# OhmmeterV1_1.net
KiCad netlist of a schematic drawn in EasyEDA Pro
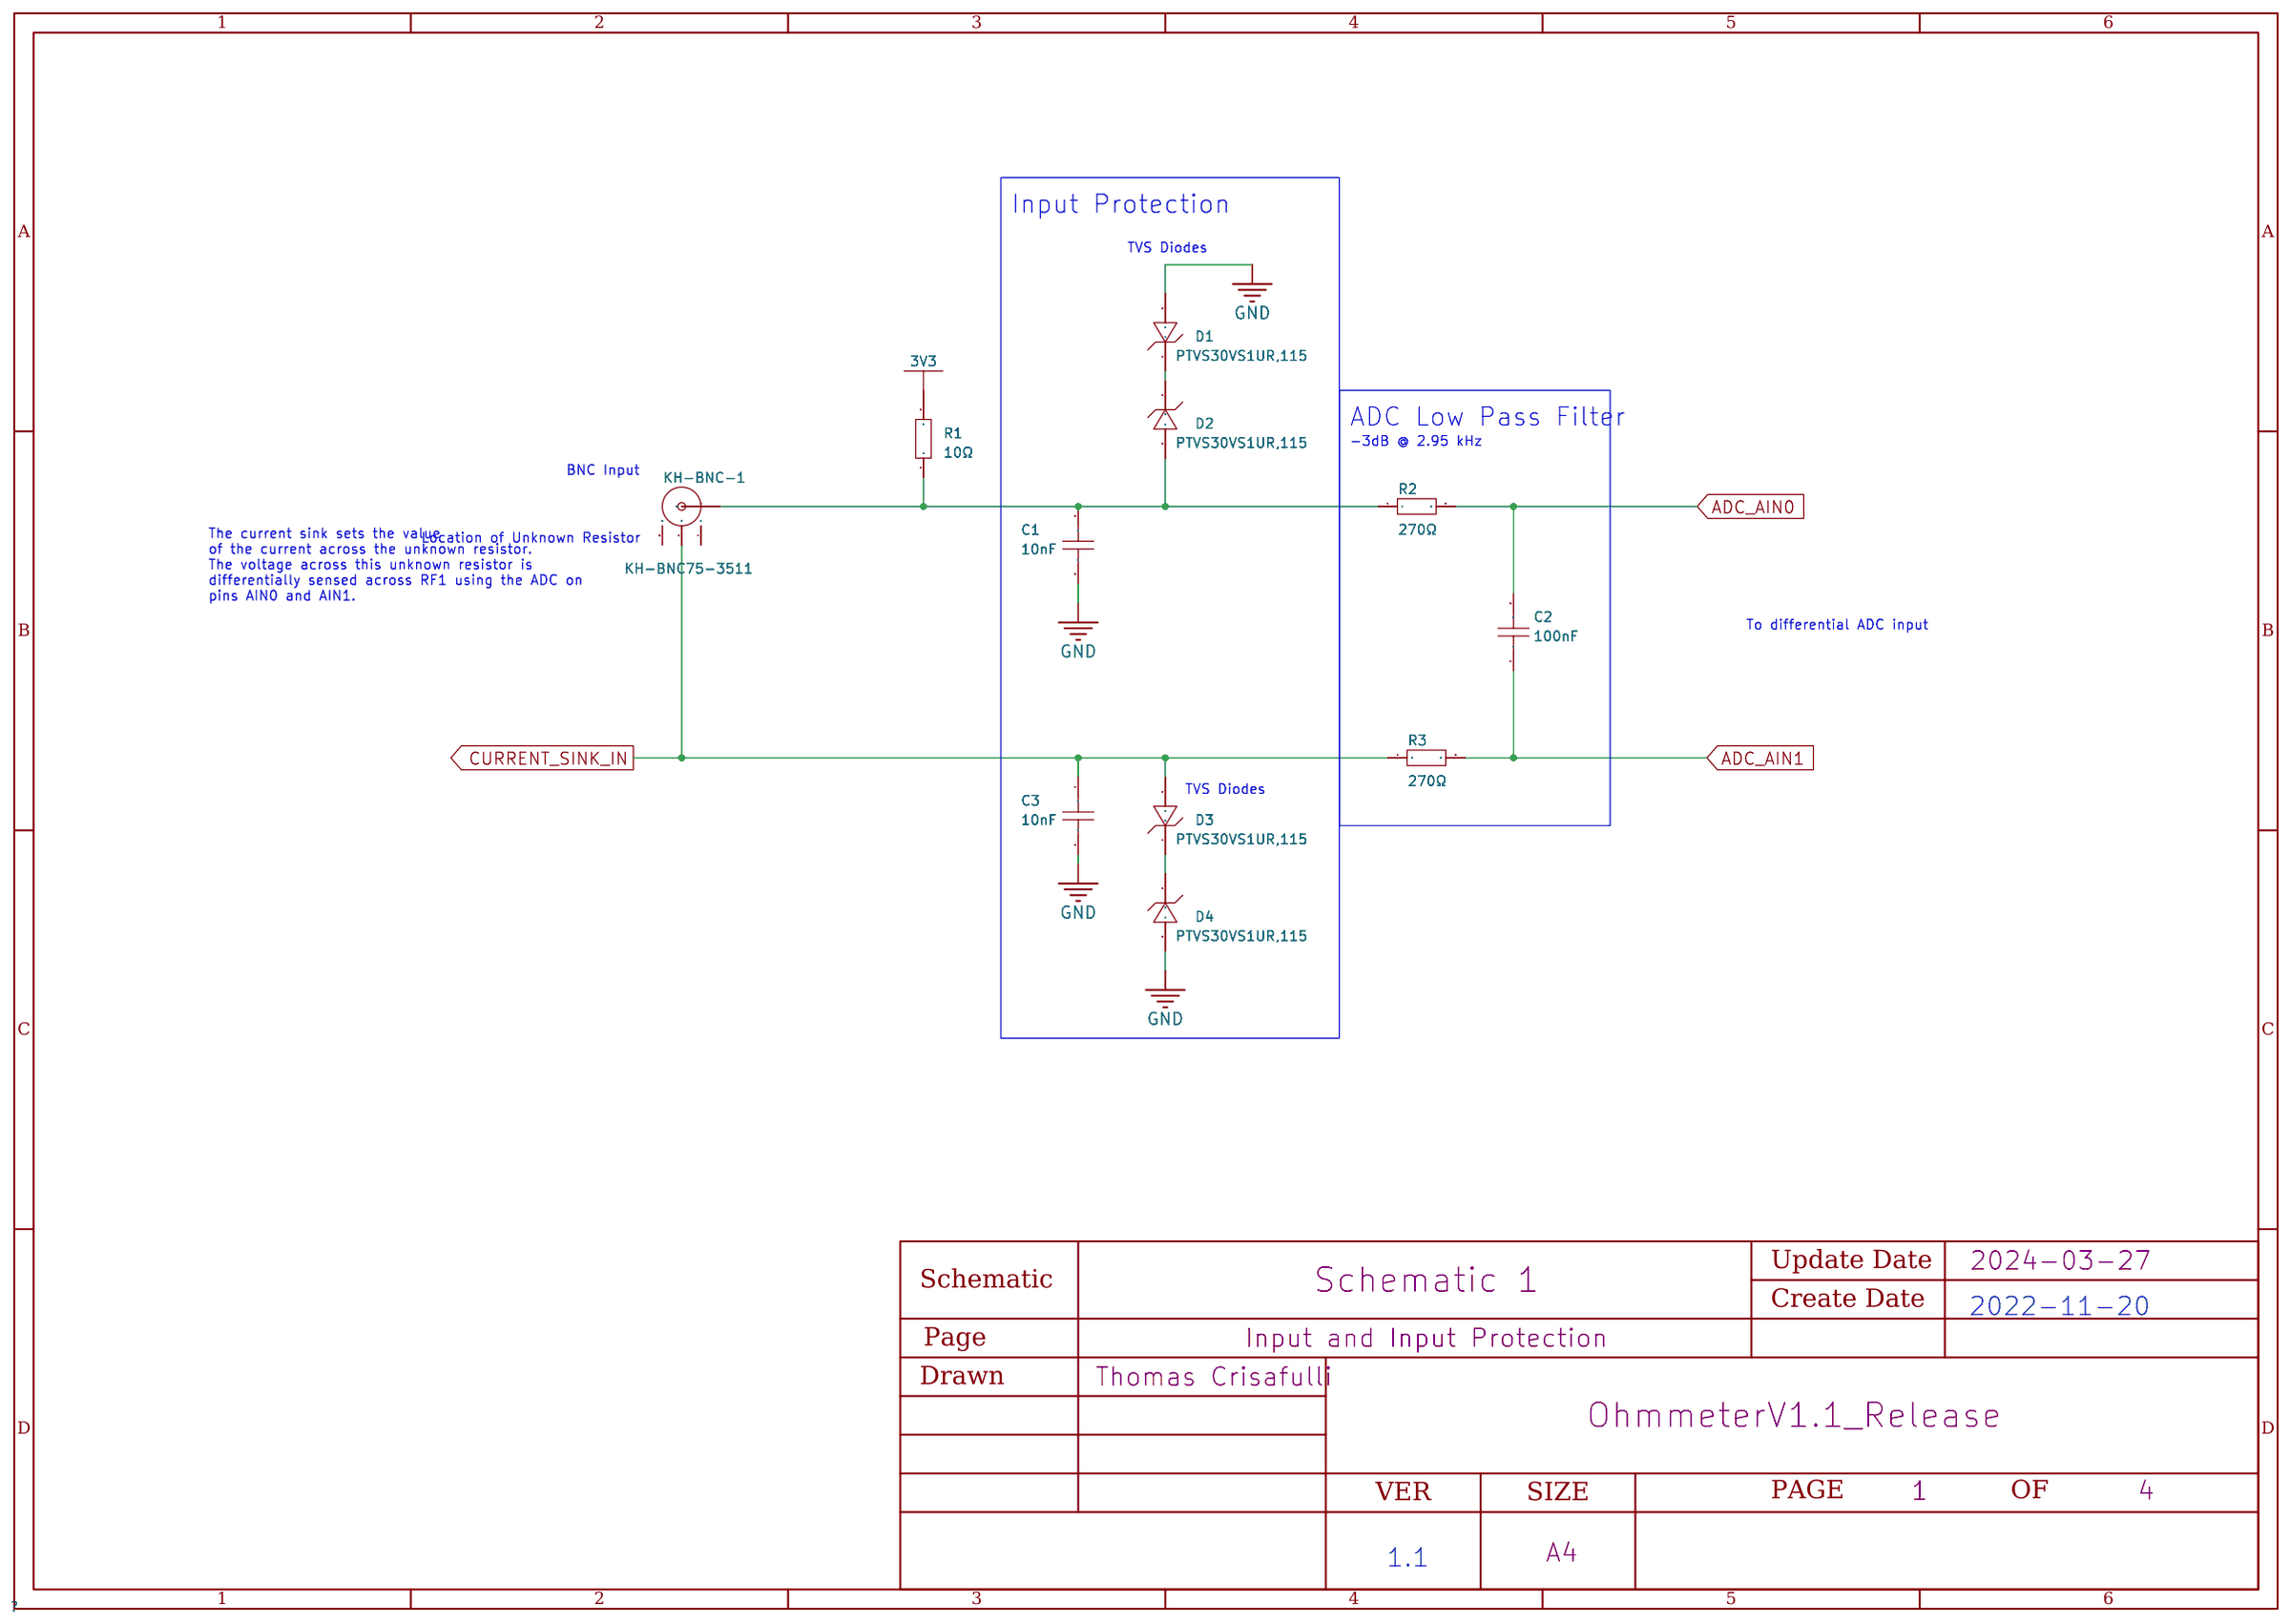
[diagram p0: Input and Input Protection]
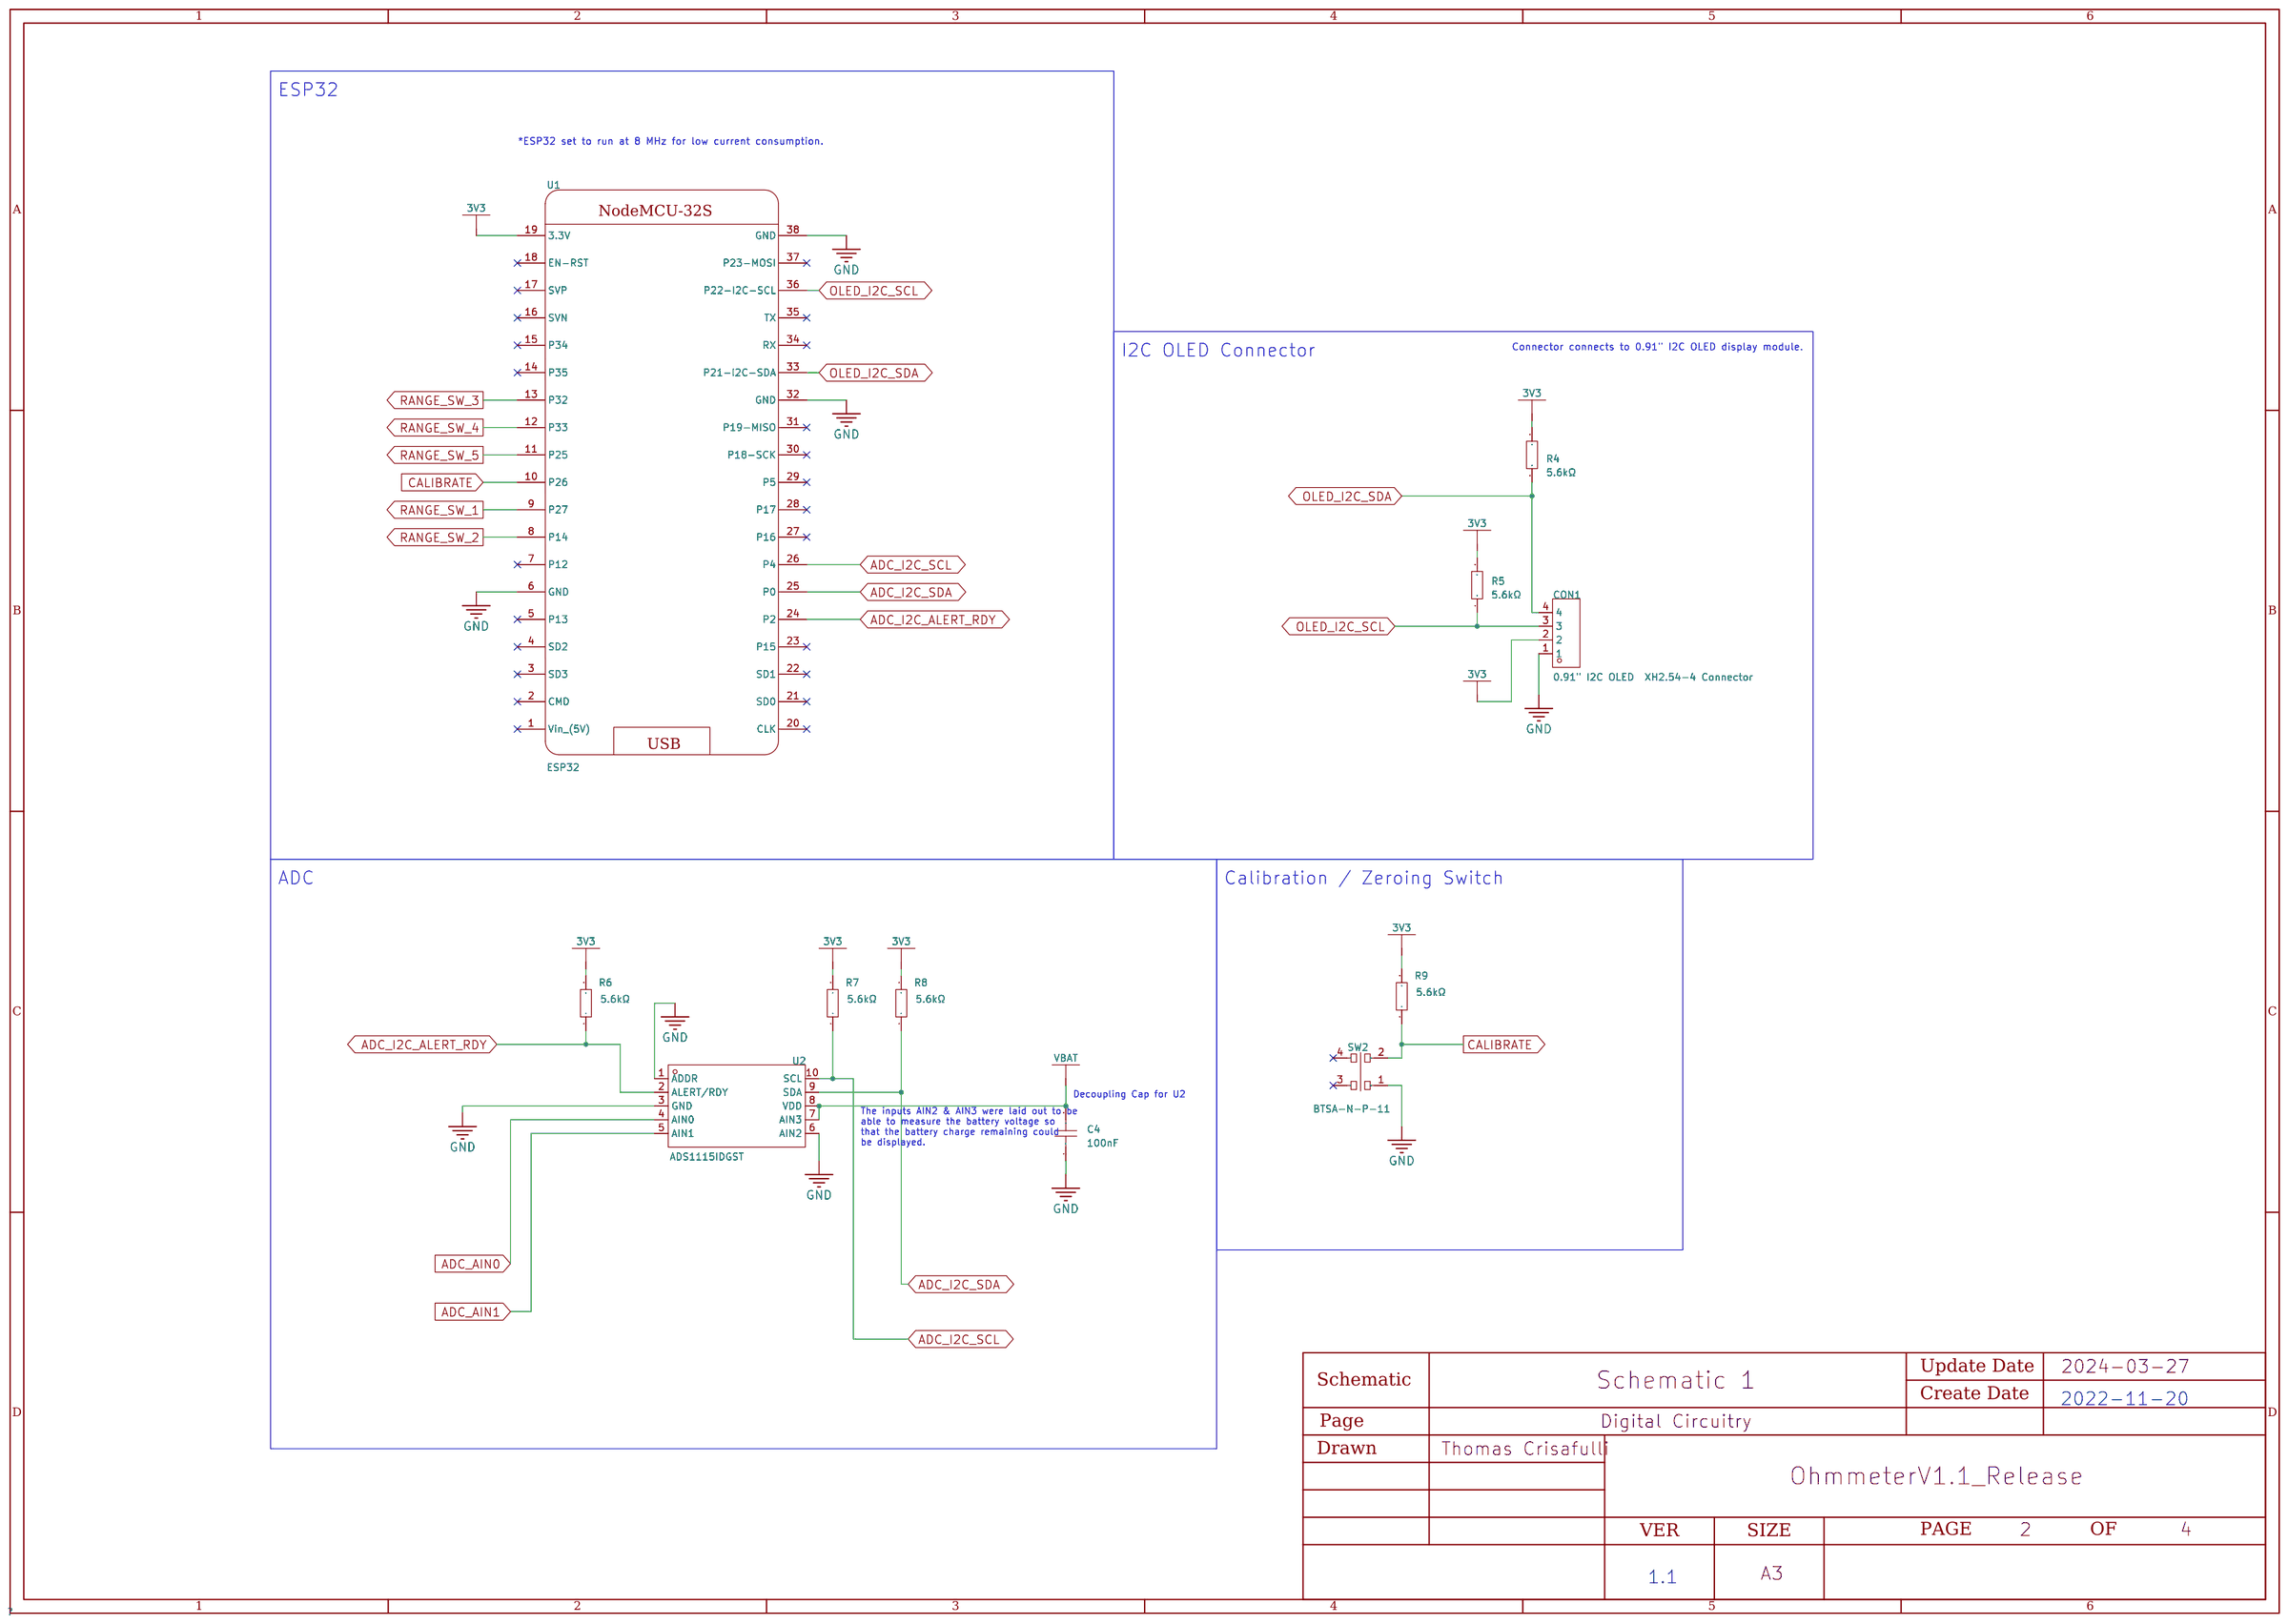
[diagram p1: Digital Circuitry]
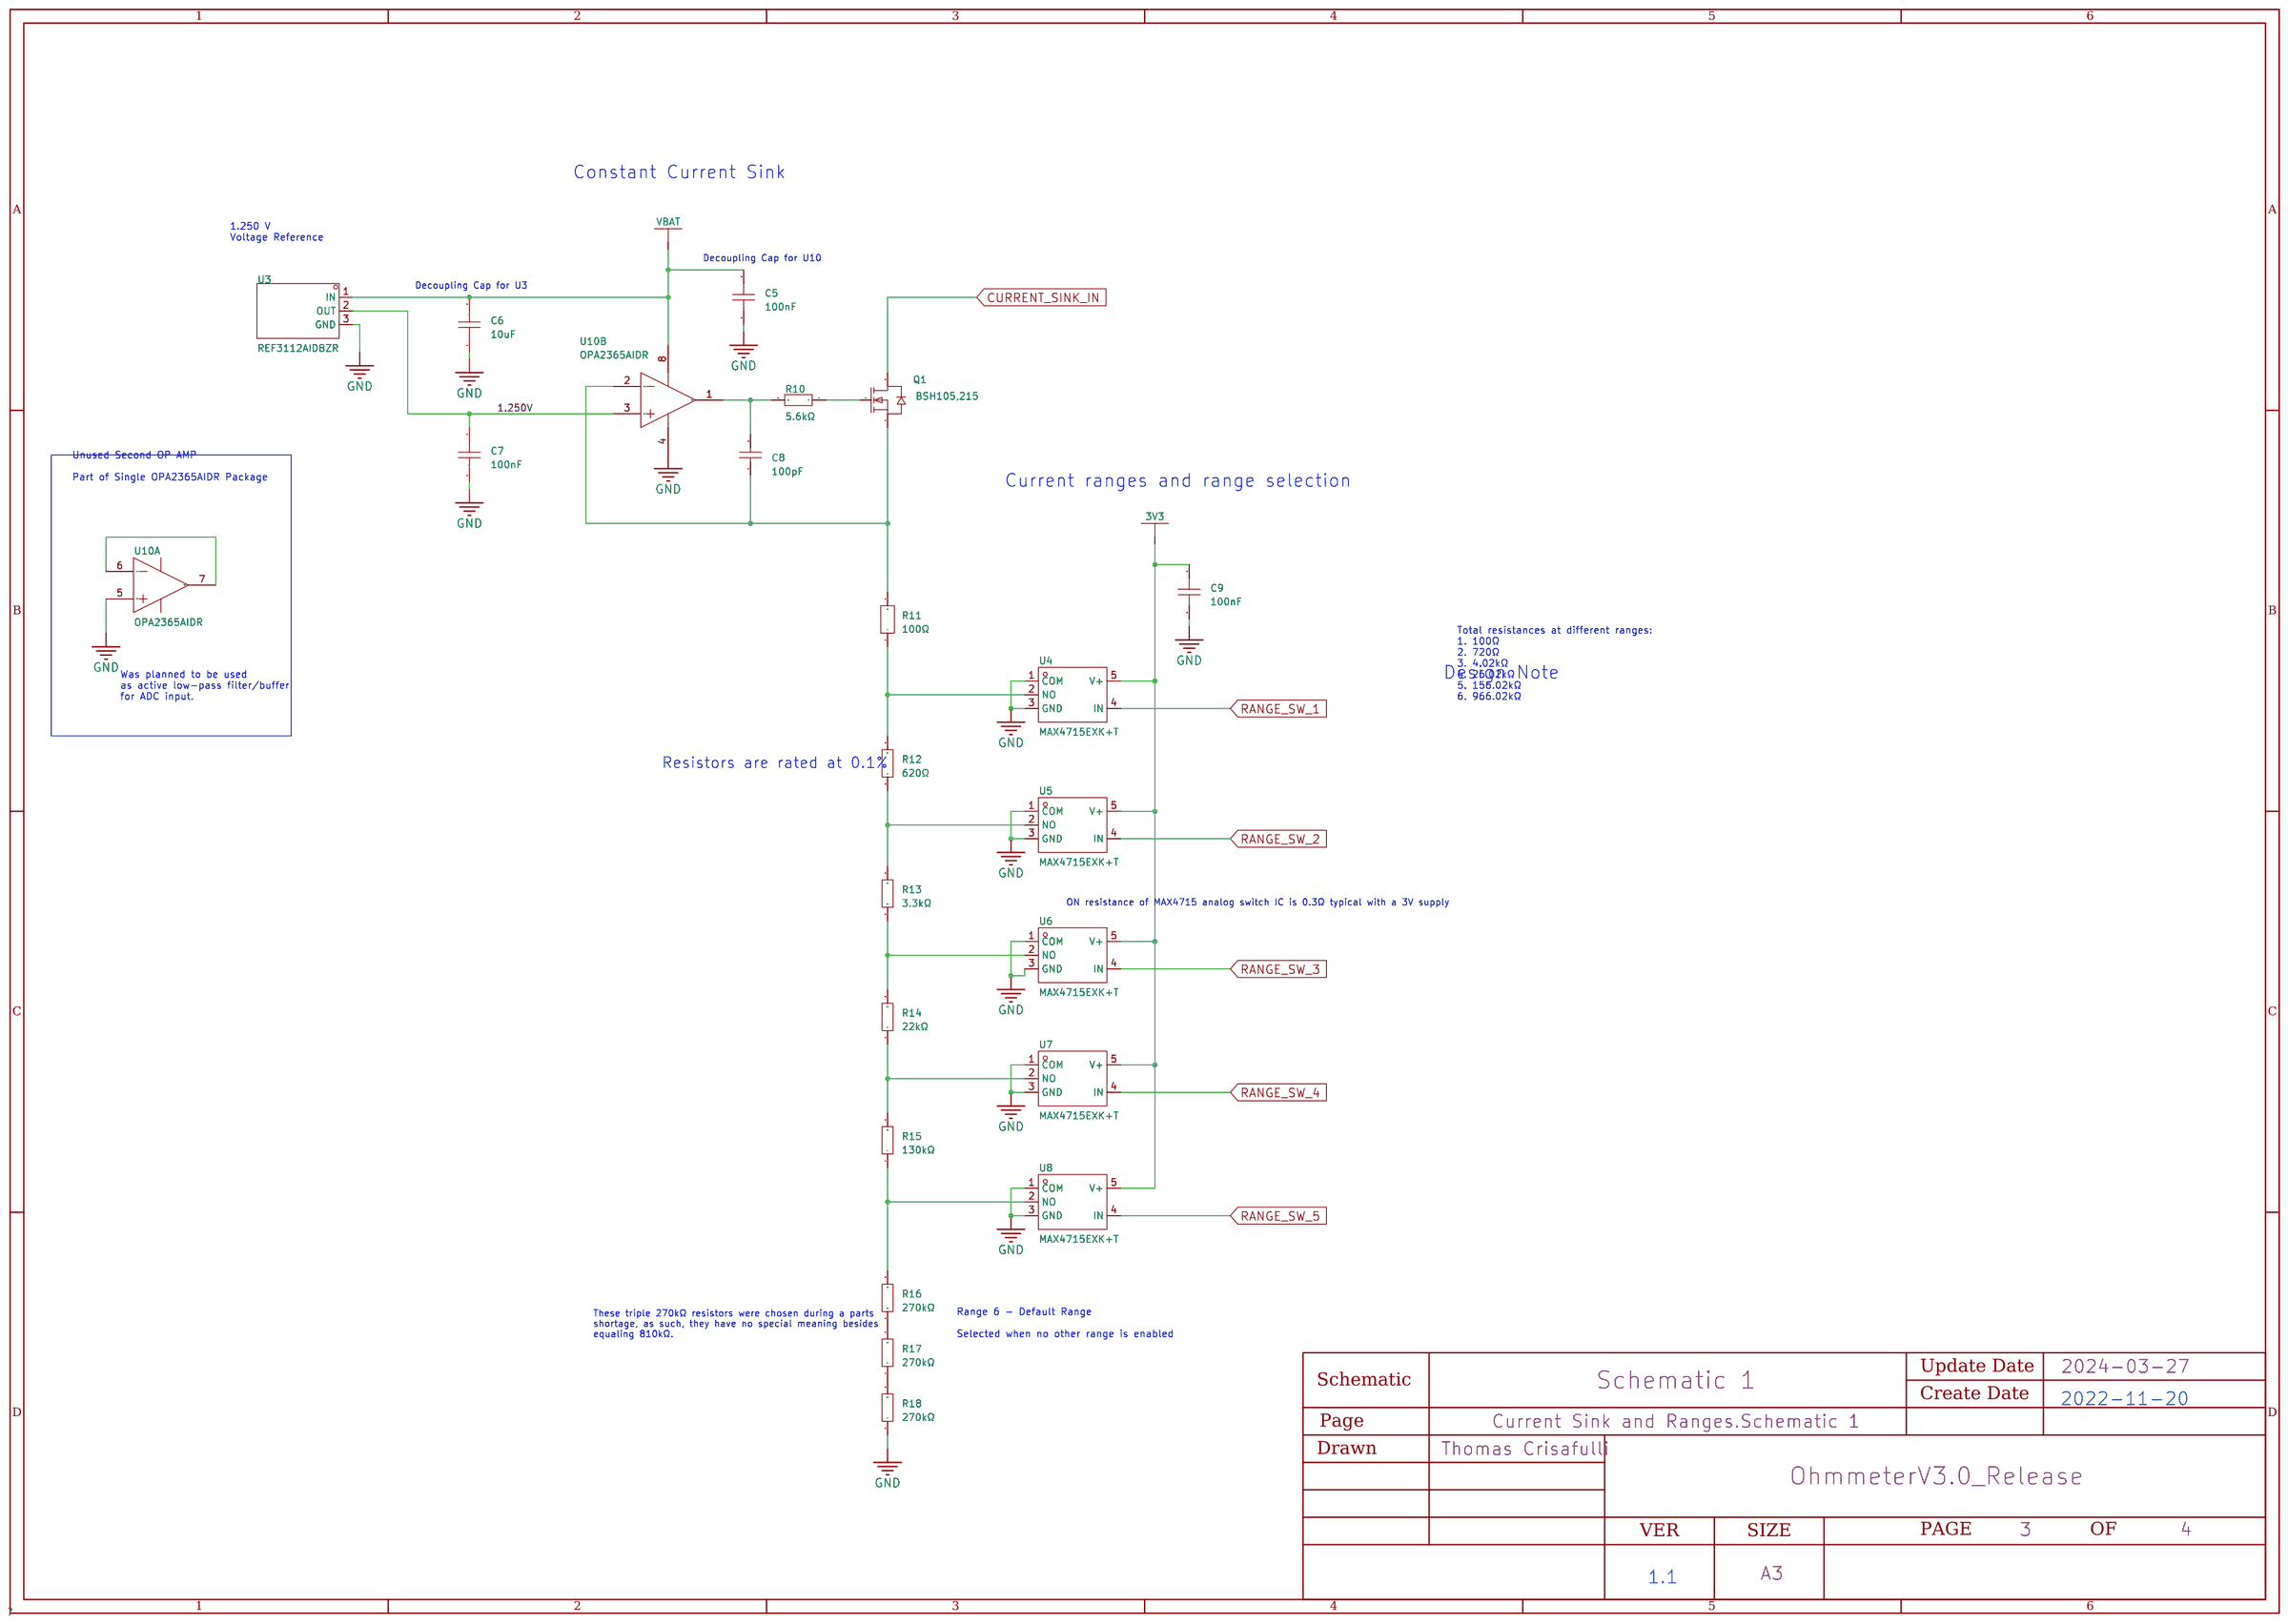
[diagram p2: Current Sink and Ranges]
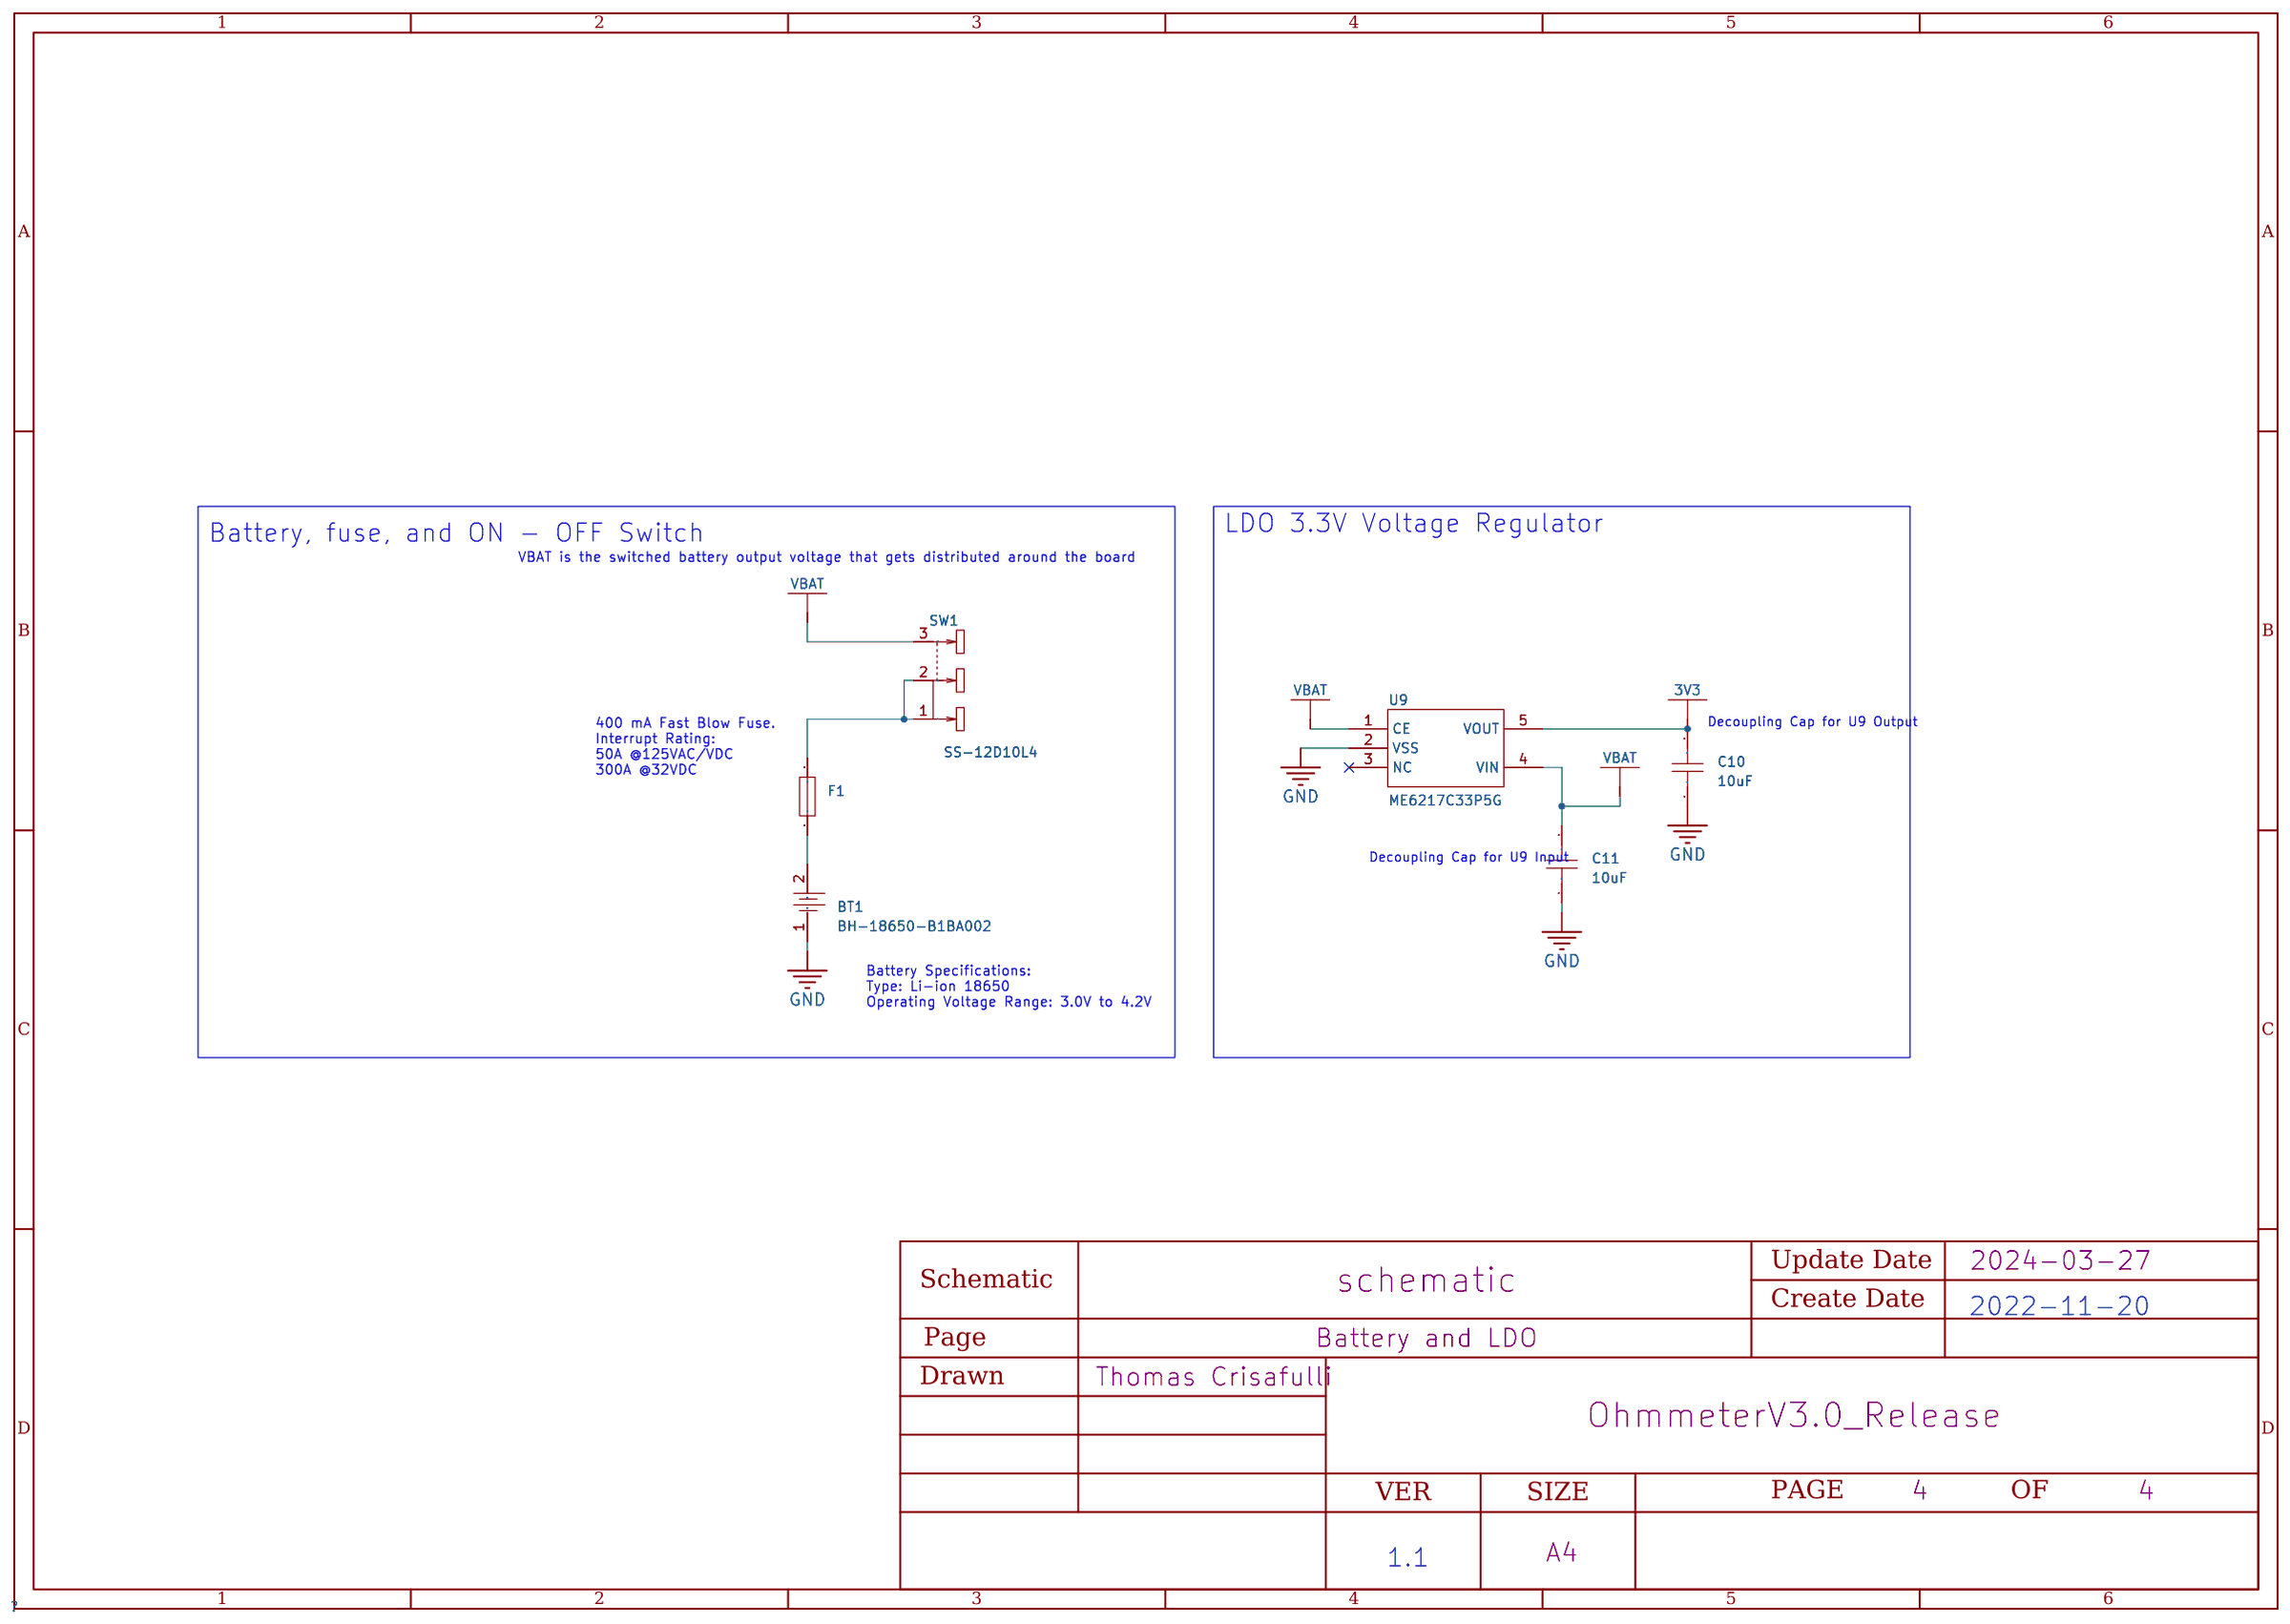
[diagram p3: Battery and LDO]

(export (version "E")
  (design (tool "Eeschema 10.0.6"))
  (components
    (comp (ref "C1")
      (value "10nF")
      (footprint "easyedapro:C0603")
      (fields (field (name "Manufacturer Part") "06031C103K4T2A") (field (name "Manufacturer") "Kyocera AVX"))
      (libsource (lib "easyedapro") (part "06031C103K4T2A"))
    )
    (comp (ref "C2")
      (value "100nF")
      (footprint "easyedapro:C0603")
      (fields
        (field (name "Manufacturer Part") "CC0603KRX7R9BB104")
        (field (name "Manufacturer") "YAGEO(国巨)")
      )
      (libsource (lib "easyedapro") (part "CC0603KRX7R9BB104"))
    )
    (comp (ref "C3")
      (value "10nF")
      (footprint "easyedapro:C0603")
      (fields (field (name "Manufacturer Part") "06031C103K4T2A") (field (name "Manufacturer") "Kyocera AVX"))
      (libsource (lib "easyedapro") (part "06031C103K4T2A"))
    )
    (comp (ref "D1")
      (value "PTVS30VS1UR,115")
      (footprint "easyedapro:SOD-123_L2.6-W1.7-LS3.5-RD")
      (fields (field (name "Manufacturer") "Nexperia(安世)"))
      (libsource (lib "easyedapro") (part "PTVS30VS1UR,115"))
    )
    (comp (ref "D2")
      (value "PTVS30VS1UR,115")
      (footprint "easyedapro:SOD-123_L2.6-W1.7-LS3.5-RD")
      (fields (field (name "Manufacturer") "Nexperia(安世)"))
      (libsource (lib "easyedapro") (part "PTVS30VS1UR,115"))
    )
    (comp (ref "D3")
      (value "PTVS30VS1UR,115")
      (footprint "easyedapro:SOD-123_L2.6-W1.7-LS3.5-RD")
      (fields (field (name "Manufacturer") "Nexperia(安世)"))
      (libsource (lib "easyedapro") (part "PTVS30VS1UR,115"))
    )
    (comp (ref "D4")
      (value "PTVS30VS1UR,115")
      (footprint "easyedapro:SOD-123_L2.6-W1.7-LS3.5-RD")
      (fields (field (name "Manufacturer") "Nexperia(安世)"))
      (libsource (lib "easyedapro") (part "PTVS30VS1UR,115"))
    )
    (comp (ref "KH-BNC-1")
      (value "KH-BNC75-3511")
      (footprint "easyedapro:ANT-TH_KH-BNC75-3511")
      (fields (field (name "Manufacturer") "kinghelm(金航标)"))
      (libsource (lib "easyedapro") (part "KH-BNC75-3511"))
    )
    (comp (ref "R1")
      (value "10Ω")
      (footprint "easyedapro:R0603")
      (fields (field (name "Manufacturer Part") "AC0603FR-0710RL") (field (name "Manufacturer") "YAGEO(国巨)"))
      (libsource (lib "easyedapro") (part "AC0603FR-0710RL"))
    )
    (comp (ref "R2")
      (value "270Ω")
      (footprint "easyedapro:R0603")
      (fields (field (name "Manufacturer Part") "RS-03K2700FT") (field (name "Manufacturer") "FH(风华)"))
      (libsource (lib "easyedapro") (part "RS-03K2700FT"))
    )
    (comp (ref "R3")
      (value "270Ω")
      (footprint "easyedapro:R0603")
      (fields (field (name "Manufacturer Part") "RS-03K2700FT") (field (name "Manufacturer") "FH(风华)"))
      (libsource (lib "easyedapro") (part "RS-03K2700FT"))
    )
    (comp (ref "C4")
      (value "100nF")
      (footprint "easyedapro:C0603")
      (fields
        (field (name "Manufacturer Part") "CC0603KRX7R9BB104")
        (field (name "Manufacturer") "YAGEO(国巨)")
      )
      (libsource (lib "easyedapro") (part "CC0603KRX7R9BB104"))
    )
    (comp (ref "CON1")
      (value "0.91\" I2C OLED  XH2.54-4 Connector")
      (footprint "easyedapro:CONN-TH_XH2.54-4")
      (libsource (lib "easyedapro") (part "XH2.54-4"))
    )
    (comp (ref "R4")
      (value "5.6kΩ")
      (footprint "easyedapro:R0603")
      (description "Resistance:5.6kΩ Tolerance:±1% Power(Watts):0.1W")
      (fields (field (name "Manufacturer Part") "RMC06035.6K1%N") (field (name "Manufacturer") "Tyohm(幸亚电阻)"))
      (libsource (lib "easyedapro") (part "RMC06035.6K1%N"))
    )
    (comp (ref "R5")
      (value "5.6kΩ")
      (footprint "easyedapro:R0603")
      (description "Resistance:5.6kΩ Tolerance:±1% Power(Watts):0.1W")
      (fields (field (name "Manufacturer Part") "RMC06035.6K1%N") (field (name "Manufacturer") "Tyohm(幸亚电阻)"))
      (libsource (lib "easyedapro") (part "RMC06035.6K1%N"))
    )
    (comp (ref "R6")
      (value "5.6kΩ")
      (footprint "easyedapro:R0603")
      (description "Resistance:5.6kΩ Tolerance:±1% Power(Watts):0.1W")
      (fields (field (name "Manufacturer Part") "RMC06035.6K1%N") (field (name "Manufacturer") "Tyohm(幸亚电阻)"))
      (libsource (lib "easyedapro") (part "RMC06035.6K1%N"))
    )
    (comp (ref "R7")
      (value "5.6kΩ")
      (footprint "easyedapro:R0603")
      (description "Resistance:5.6kΩ Tolerance:±1% Power(Watts):0.1W")
      (fields (field (name "Manufacturer Part") "RMC06035.6K1%N") (field (name "Manufacturer") "Tyohm(幸亚电阻)"))
      (libsource (lib "easyedapro") (part "RMC06035.6K1%N"))
    )
    (comp (ref "R8")
      (value "5.6kΩ")
      (footprint "easyedapro:R0603")
      (description "Resistance:5.6kΩ Tolerance:±1% Power(Watts):0.1W")
      (fields (field (name "Manufacturer Part") "RMC06035.6K1%N") (field (name "Manufacturer") "Tyohm(幸亚电阻)"))
      (libsource (lib "easyedapro") (part "RMC06035.6K1%N"))
    )
    (comp (ref "R9")
      (value "5.6kΩ")
      (footprint "easyedapro:R0603")
      (description "Resistance:5.6kΩ Tolerance:±1% Power(Watts):0.1W")
      (fields (field (name "Manufacturer Part") "RMC06035.6K1%N") (field (name "Manufacturer") "Tyohm(幸亚电阻)"))
      (libsource (lib "easyedapro") (part "RMC06035.6K1%N"))
    )
    (comp (ref "SW2")
      (value "BTSA-N-P-11")
      (footprint "easyedapro:SW-TH_BTSA-X-P-11")
      (fields (field (name "Manufacturer") "ROCPU Switches(台普)"))
      (libsource (lib "easyedapro") (part "BTSA-N-P-11_C2888323"))
    )
    (comp (ref "U1")
      (value "ESP32")
      (footprint "easyedapro:NODEMCU-32SLUA")
      (fields (field (name "Manufacturer Part") "NodeMCU-32SLua") (field (name "Manufacturer") "Ai-Thinker"))
      (libsource (lib "easyedapro") (part "ESP32"))
    )
    (comp (ref "U2")
      (value "ADS1115IDGST")
      (footprint "easyedapro:VSSOP-10_L3.0-W3.0-P0.50-LS4.9-BL")
      (fields (field (name "Manufacturer") "TI(德州仪器)"))
      (libsource (lib "easyedapro") (part "ADS1115IDGST"))
    )
    (comp (ref "C5")
      (value "100nF")
      (footprint "easyedapro:C0603")
      (fields
        (field (name "Manufacturer Part") "CC0603KRX7R9BB104")
        (field (name "Manufacturer") "YAGEO(国巨)")
      )
      (libsource (lib "easyedapro") (part "CC0603KRX7R9BB104"))
    )
    (comp (ref "C6")
      (value "10uF")
      (footprint "easyedapro:C0603")
      (fields
        (field (name "Manufacturer Part") "CL10A106KP8NNNC")
        (field (name "Manufacturer") "SAMSUNG(三星)")
      )
      (libsource (lib "easyedapro") (part "CL10A106KP8NNNC"))
    )
    (comp (ref "C7")
      (value "100nF")
      (footprint "easyedapro:C0603")
      (fields
        (field (name "Manufacturer Part") "CC0603KRX7R9BB104")
        (field (name "Manufacturer") "YAGEO(国巨)")
      )
      (libsource (lib "easyedapro") (part "CC0603KRX7R9BB104"))
    )
    (comp (ref "C8")
      (value "100pF")
      (footprint "easyedapro:C0603")
      (fields (field (name "Manufacturer Part") "0603CG101F500NT") (field (name "Manufacturer") "FH(风华)"))
      (libsource (lib "easyedapro") (part "0603CG101F500NT"))
    )
    (comp (ref "C9")
      (value "100nF")
      (footprint "easyedapro:C0603")
      (fields
        (field (name "Manufacturer Part") "CC0603KRX7R9BB104")
        (field (name "Manufacturer") "YAGEO(国巨)")
      )
      (libsource (lib "easyedapro") (part "CC0603KRX7R9BB104"))
    )
    (comp (ref "Q1")
      (value "BSH105,215")
      (footprint "easyedapro:TO-236AB_L2.9-W1.3-P0.95-LS2.3-BR")
      (fields (field (name "Manufacturer") "Nexperia(安世)"))
      (libsource (lib "easyedapro") (part "BSH105,215"))
    )
    (comp (ref "R10")
      (value "5.6kΩ")
      (footprint "easyedapro:R0603")
      (description "Resistance:5.6kΩ Tolerance:±1% Power(Watts):0.1W")
      (fields (field (name "Manufacturer Part") "RMC06035.6K1%N") (field (name "Manufacturer") "Tyohm(幸亚电阻)"))
      (libsource (lib "easyedapro") (part "RMC06035.6K1%N"))
    )
    (comp (ref "R11")
      (value "100Ω")
      (footprint "easyedapro:R0805")
      (fields (field (name "Manufacturer Part") "RT0805BRB07100RL") (field (name "Manufacturer") "YAGEO(国巨)"))
      (libsource (lib "easyedapro") (part "RT0805BRB07100RL"))
    )
    (comp (ref "R12")
      (value "620Ω")
      (footprint "easyedapro:R0805")
      (fields (field (name "Manufacturer Part") "PTFR0805B620RN9") (field (name "Manufacturer") "RESI(开步睿思）"))
      (libsource (lib "easyedapro") (part "PTFR0805B620RN9"))
    )
    (comp (ref "R13")
      (value "3.3kΩ")
      (footprint "easyedapro:R0805")
      (fields (field (name "Manufacturer Part") "PTFR0805B3K30N9") (field (name "Manufacturer") "RESI(开步睿思）"))
      (libsource (lib "easyedapro") (part "PTFR0805B3K30N9"))
    )
    (comp (ref "R14")
      (value "22kΩ")
      (footprint "easyedapro:R0805")
      (fields (field (name "Manufacturer Part") "PTFR0805B22K0N9") (field (name "Manufacturer") "RESI(开步睿思）"))
      (libsource (lib "easyedapro") (part "PTFR0805B22K0N9"))
    )
    (comp (ref "R15")
      (value "130kΩ")
      (footprint "easyedapro:R0805")
      (fields (field (name "Manufacturer Part") "PTFR0805B130KN9") (field (name "Manufacturer") "RESI(开步睿思）"))
      (libsource (lib "easyedapro") (part "PTFR0805B130KN9"))
    )
    (comp (ref "R16")
      (value "270kΩ")
      (footprint "easyedapro:R0805")
      (fields (field (name "Manufacturer Part") "PTFR0805B270KN9") (field (name "Manufacturer") "RESI(开步睿思）"))
      (libsource (lib "easyedapro") (part "PTFR0805B270KN9"))
    )
    (comp (ref "R17")
      (value "270kΩ")
      (footprint "easyedapro:R0805")
      (fields (field (name "Manufacturer Part") "PTFR0805B270KN9") (field (name "Manufacturer") "RESI(开步睿思）"))
      (libsource (lib "easyedapro") (part "PTFR0805B270KN9"))
    )
    (comp (ref "R18")
      (value "270kΩ")
      (footprint "easyedapro:R0805")
      (fields (field (name "Manufacturer Part") "PTFR0805B270KN9") (field (name "Manufacturer") "RESI(开步睿思）"))
      (libsource (lib "easyedapro") (part "PTFR0805B270KN9"))
    )
    (comp (ref "U3")
      (value "REF3112AIDBZR")
      (footprint "easyedapro:SOT-23-3_L2.9-W1.6-P1.90-LS2.8-BR")
      (fields (field (name "Manufacturer") "TI(德州仪器)"))
      (libsource (lib "easyedapro") (part "REF3112AIDBZR"))
    )
    (comp (ref "U4")
      (value "MAX4715EXK+T")
      (footprint "easyedapro:SC-70-5_L2.0-W1.3-P0.65-LS2.1-BR")
      (fields (field (name "Manufacturer") "MAXIM(美信)"))
      (libsource (lib "easyedapro") (part "MAX4715EXK+T"))
    )
    (comp (ref "U5")
      (value "MAX4715EXK+T")
      (footprint "easyedapro:SC-70-5_L2.0-W1.3-P0.65-LS2.1-BR")
      (fields (field (name "Manufacturer") "MAXIM(美信)"))
      (libsource (lib "easyedapro") (part "MAX4715EXK+T"))
    )
    (comp (ref "U6")
      (value "MAX4715EXK+T")
      (footprint "easyedapro:SC-70-5_L2.0-W1.3-P0.65-LS2.1-BR")
      (fields (field (name "Manufacturer") "MAXIM(美信)"))
      (libsource (lib "easyedapro") (part "MAX4715EXK+T"))
    )
    (comp (ref "U7")
      (value "MAX4715EXK+T")
      (footprint "easyedapro:SC-70-5_L2.0-W1.3-P0.65-LS2.1-BR")
      (fields (field (name "Manufacturer") "MAXIM(美信)"))
      (libsource (lib "easyedapro") (part "MAX4715EXK+T"))
    )
    (comp (ref "U8")
      (value "MAX4715EXK+T")
      (footprint "easyedapro:SC-70-5_L2.0-W1.3-P0.65-LS2.1-BR")
      (fields (field (name "Manufacturer") "MAXIM(美信)"))
      (libsource (lib "easyedapro") (part "MAX4715EXK+T"))
    )
    (comp (ref "U10")
      (value "OPA2365AIDR")
      (footprint "easyedapro:SOIC-8_L4.9-W3.9-P1.27-LS6.0-BL")
      (fields (field (name "Manufacturer") "TI(德州仪器)"))
      (libsource (lib "easyedapro") (part "OPA2365AIDR"))
    )
    (comp (ref "BT1")
      (value "BH-18650-B1BA002")
      (footprint "easyedapro:BATTERY-SMD_18650-1S-L77.1-W20.7-1")
      (fields (field (name "Manufacturer") "MYOUNG(美阳)"))
      (libsource (lib "easyedapro") (part "BH-18650-B1BA002"))
    )
    (comp (ref "C10")
      (value "10uF")
      (footprint "easyedapro:C0603")
      (fields
        (field (name "Manufacturer Part") "CL10A106KP8NNNC")
        (field (name "Manufacturer") "SAMSUNG(三星)")
      )
      (libsource (lib "easyedapro") (part "CL10A106KP8NNNC"))
    )
    (comp (ref "C11")
      (value "10uF")
      (footprint "easyedapro:C0603")
      (fields
        (field (name "Manufacturer Part") "CL10A106KP8NNNC")
        (field (name "Manufacturer") "SAMSUNG(三星)")
      )
      (libsource (lib "easyedapro") (part "CL10A106KP8NNNC"))
    )
    (comp (ref "F1")
      (value "~")
      (footprint "easyedapro:0451.400MRL")
      (description "400 mA Fast Blow Fuse. Interrupt Rating: 50A @125VAC/VDC\n300A @32VDC")
      (libsource (lib "easyedapro") (part "0451.400MRL"))
    )
    (comp (ref "SW1")
      (value "SS-12D10L4")
      (footprint "easyedapro:SW-TH_SS-12D10L3")
      (fields (field (name "Manufacturer") "XKB Connectivity(中国星坤)"))
      (libsource (lib "easyedapro") (part "SS-12D10L4"))
    )
    (comp (ref "U9")
      (value "ME6217C33P5G")
      (footprint "easyedapro:SOT-89-5_L4.5-W2.5-P1.50-LS4.5-BR")
      (fields (field (name "Manufacturer") "MICRONE(南京微盟)"))
      (libsource (lib "easyedapro") (part "ME6217C33P5G"))
    )
  )
  (nets
    (net (code "1") (name "1.250V") (class "Default")
      (node (ref "C7") (pin "1") (pinfunction "1_1") (pintype "input"))
      (node (ref "U10") (pin "3") (pinfunction "IN_A+_3") (pintype "input"))
      (node (ref "U3") (pin "2") (pinfunction "OUT_2") (pintype "input"))
    )
    (net (code "2") (name "3V3") (class "Default")
      (node (ref "C10") (pin "2") (pinfunction "2_2") (pintype "input"))
      (node (ref "C9") (pin "2") (pinfunction "2_2") (pintype "input"))
      (node (ref "CON1") (pin "2") (pinfunction "2_2") (pintype "input"))
      (node (ref "R1") (pin "2") (pinfunction "2_2") (pintype "unspecified"))
      (node (ref "R4") (pin "1") (pinfunction "1_1") (pintype "input"))
      (node (ref "R5") (pin "2") (pinfunction "2_2") (pintype "input"))
      (node (ref "R6") (pin "2") (pinfunction "2_2") (pintype "input"))
      (node (ref "R7") (pin "2") (pinfunction "2_2") (pintype "input"))
      (node (ref "R8") (pin "2") (pinfunction "2_2") (pintype "input"))
      (node (ref "R9") (pin "2") (pinfunction "2_2") (pintype "input"))
      (node (ref "U1") (pin "19") (pinfunction "3.3V_19") (pintype "input"))
      (node (ref "U4") (pin "5") (pinfunction "V+_5") (pintype "input"))
      (node (ref "U5") (pin "5") (pinfunction "V+_5") (pintype "input"))
      (node (ref "U6") (pin "5") (pinfunction "V+_5") (pintype "input"))
      (node (ref "U7") (pin "5") (pinfunction "V+_5") (pintype "input"))
      (node (ref "U8") (pin "5") (pinfunction "V+_5") (pintype "input"))
      (node (ref "U9") (pin "5") (pinfunction "VOUT_5") (pintype "input"))
    )
    (net (code "3") (name "ADC_AIN0") (class "Default")
      (node (ref "C2") (pin "2") (pinfunction "2_2") (pintype "input"))
      (node (ref "R2") (pin "2") (pinfunction "2_2") (pintype "input"))
      (node (ref "U2") (pin "4") (pinfunction "AIN0_4") (pintype "input"))
    )
    (net (code "4") (name "ADC_AIN1") (class "Default")
      (node (ref "C2") (pin "1") (pinfunction "1_1") (pintype "input"))
      (node (ref "R3") (pin "2") (pinfunction "2_2") (pintype "input"))
      (node (ref "U2") (pin "5") (pinfunction "AIN1_5") (pintype "input"))
    )
    (net (code "5") (name "ADC_I2C_ALERT_RDY") (class "Default")
      (node (ref "R6") (pin "1") (pinfunction "1_1") (pintype "input"))
      (node (ref "U1") (pin "24") (pinfunction "P2_24") (pintype "input"))
      (node (ref "U2") (pin "2") (pinfunction "ALERT/RDY_2") (pintype "input"))
    )
    (net (code "6") (name "ADC_I2C_SCL") (class "Default")
      (node (ref "R7") (pin "1") (pinfunction "1_1") (pintype "input"))
      (node (ref "U1") (pin "26") (pinfunction "P4_26") (pintype "input"))
      (node (ref "U2") (pin "10") (pinfunction "SCL_10") (pintype "input"))
    )
    (net (code "7") (name "ADC_I2C_SDA") (class "Default")
      (node (ref "R8") (pin "1") (pinfunction "1_1") (pintype "input"))
      (node (ref "U1") (pin "25") (pinfunction "P0_25") (pintype "input"))
      (node (ref "U2") (pin "9") (pinfunction "SDA_9") (pintype "input"))
    )
    (net (code "8") (name "CALIBRATE") (class "Default")
      (node (ref "R9") (pin "1") (pinfunction "1_1") (pintype "input"))
      (node (ref "SW2") (pin "2") (pinfunction "2_2") (pintype "input"))
      (node (ref "U1") (pin "10") (pinfunction "P26_10") (pintype "input"))
    )
    (net (code "9") (name "CURRENT_SINK_IN") (class "Default")
      (node (ref "C3") (pin "1") (pinfunction "1_1") (pintype "input"))
      (node (ref "D3") (pin "2") (pinfunction "A_2") (pintype "input"))
      (node (ref "KH-BNC-1") (pin "2") (pinfunction "2_2") (pintype "input"))
      (node (ref "Q1") (pin "3") (pinfunction "D_3") (pintype "input"))
      (node (ref "R3") (pin "1") (pinfunction "1_1") (pintype "input"))
    )
    (net (code "10") (name "GND") (class "Default")
      (node (ref "BT1") (pin "1") (pinfunction "1_1") (pintype "input"))
      (node (ref "C1") (pin "2") (pinfunction "2_2") (pintype "input"))
      (node (ref "C10") (pin "1") (pinfunction "1_1") (pintype "input"))
      (node (ref "C11") (pin "1") (pinfunction "1_1") (pintype "input"))
      (node (ref "C3") (pin "2") (pinfunction "2_2") (pintype "input"))
      (node (ref "C4") (pin "1") (pinfunction "1_1") (pintype "input"))
      (node (ref "C5") (pin "1") (pinfunction "1_1") (pintype "input"))
      (node (ref "C6") (pin "1") (pinfunction "1_1") (pintype "input"))
      (node (ref "C7") (pin "2") (pinfunction "2_2") (pintype "input"))
      (node (ref "C9") (pin "1") (pinfunction "1_1") (pintype "input"))
      (node (ref "CON1") (pin "1") (pinfunction "1_1") (pintype "input"))
      (node (ref "D1") (pin "2") (pinfunction "A_2") (pintype "input"))
      (node (ref "D4") (pin "2") (pinfunction "A_2") (pintype "input"))
      (node (ref "R18") (pin "1") (pinfunction "1_1") (pintype "input"))
      (node (ref "SW2") (pin "1") (pinfunction "1_1") (pintype "input"))
      (node (ref "U1") (pin "32") (pinfunction "GND_32") (pintype "input"))
      (node (ref "U1") (pin "38") (pinfunction "GND_38") (pintype "input"))
      (node (ref "U1") (pin "6") (pinfunction "GND_6") (pintype "input"))
      (node (ref "U10") (pin "4") (pinfunction "V-_4") (pintype "input"))
      (node (ref "U10") (pin "5") (pinfunction "IN_B+_5") (pintype "input"))
      (node (ref "U2") (pin "1") (pinfunction "ADDR_1") (pintype "input"))
      (node (ref "U2") (pin "3") (pinfunction "GND_3") (pintype "input"))
      (node (ref "U2") (pin "6") (pinfunction "AIN2_6") (pintype "input"))
      (node (ref "U3") (pin "3") (pinfunction "GND_3") (pintype "input"))
      (node (ref "U4") (pin "1") (pinfunction "COM_1") (pintype "input"))
      (node (ref "U4") (pin "3") (pinfunction "GND_3") (pintype "input"))
      (node (ref "U5") (pin "1") (pinfunction "COM_1") (pintype "input"))
      (node (ref "U5") (pin "3") (pinfunction "GND_3") (pintype "input"))
      (node (ref "U6") (pin "1") (pinfunction "COM_1") (pintype "input"))
      (node (ref "U6") (pin "3") (pinfunction "GND_3") (pintype "input"))
      (node (ref "U7") (pin "1") (pinfunction "COM_1") (pintype "input"))
      (node (ref "U7") (pin "3") (pinfunction "GND_3") (pintype "input"))
      (node (ref "U8") (pin "1") (pinfunction "COM_1") (pintype "input"))
      (node (ref "U8") (pin "3") (pinfunction "GND_3") (pintype "input"))
      (node (ref "U9") (pin "2") (pinfunction "VSS_2") (pintype "input"))
    )
    (net (code "11") (name "Net-(BT1-Pad2)") (class "Default")
      (node (ref "BT1") (pin "2") (pinfunction "2_2") (pintype "input"))
      (node (ref "F1") (pin "1") (pinfunction "1_1") (pintype "input"))
    )
    (net (code "12") (name "Net-(D1-C)") (class "Default")
      (node (ref "D1") (pin "1") (pinfunction "C_1") (pintype "input"))
      (node (ref "D2") (pin "1") (pinfunction "C_1") (pintype "input"))
    )
    (net (code "13") (name "Net-(D2-A)") (class "Default")
      (node (ref "C1") (pin "1") (pinfunction "1_1") (pintype "input"))
      (node (ref "D2") (pin "2") (pinfunction "A_2") (pintype "input"))
      (node (ref "KH-BNC-1") (pin "1") (pinfunction "OUT_1") (pintype "input"))
      (node (ref "R1") (pin "1") (pinfunction "1_1") (pintype "unspecified"))
      (node (ref "R2") (pin "1") (pinfunction "1_1") (pintype "input"))
    )
    (net (code "14") (name "Net-(D3-C)") (class "Default")
      (node (ref "D3") (pin "1") (pinfunction "C_1") (pintype "input"))
      (node (ref "D4") (pin "1") (pinfunction "C_1") (pintype "input"))
    )
    (net (code "15") (name "Net-(F1-Pad2)") (class "Default")
      (node (ref "F1") (pin "2") (pinfunction "2_2") (pintype "input"))
      (node (ref "SW1") (pin "1") (pinfunction "1_1") (pintype "input"))
      (node (ref "SW1") (pin "2") (pinfunction "2_2") (pintype "input"))
    )
    (net (code "16") (name "Net-(Q1-G)") (class "Default")
      (node (ref "Q1") (pin "1") (pinfunction "G_1") (pintype "input"))
      (node (ref "R10") (pin "1") (pinfunction "1_1") (pintype "input"))
    )
    (net (code "17") (name "Net-(Q1-S)") (class "Default")
      (node (ref "C8") (pin "2") (pinfunction "2_2") (pintype "input"))
      (node (ref "Q1") (pin "2") (pinfunction "S_2") (pintype "input"))
      (node (ref "R11") (pin "2") (pinfunction "2_2") (pintype "input"))
      (node (ref "U10") (pin "2") (pinfunction "IN_A-_2") (pintype "input"))
    )
    (net (code "18") (name "Net-(R16-Pad1)") (class "Default")
      (node (ref "R16") (pin "1") (pinfunction "1_1") (pintype "input"))
      (node (ref "R17") (pin "2") (pinfunction "2_2") (pintype "input"))
    )
    (net (code "19") (name "Net-(R17-Pad1)") (class "Default")
      (node (ref "R17") (pin "1") (pinfunction "1_1") (pintype "input"))
      (node (ref "R18") (pin "2") (pinfunction "2_2") (pintype "input"))
    )
    (net (code "20") (name "Net-(U4-NO)") (class "Default")
      (node (ref "R11") (pin "1") (pinfunction "1_1") (pintype "input"))
      (node (ref "R12") (pin "2") (pinfunction "2_2") (pintype "input"))
      (node (ref "U4") (pin "2") (pinfunction "NO_2") (pintype "input"))
    )
    (net (code "21") (name "Net-(U5-NO)") (class "Default")
      (node (ref "R12") (pin "1") (pinfunction "1_1") (pintype "input"))
      (node (ref "R13") (pin "2") (pinfunction "2_2") (pintype "input"))
      (node (ref "U5") (pin "2") (pinfunction "NO_2") (pintype "input"))
    )
    (net (code "22") (name "Net-(U6-NO)") (class "Default")
      (node (ref "R13") (pin "1") (pinfunction "1_1") (pintype "input"))
      (node (ref "R14") (pin "2") (pinfunction "2_2") (pintype "input"))
      (node (ref "U6") (pin "2") (pinfunction "NO_2") (pintype "input"))
    )
    (net (code "23") (name "Net-(U7-NO)") (class "Default")
      (node (ref "R14") (pin "1") (pinfunction "1_1") (pintype "input"))
      (node (ref "R15") (pin "2") (pinfunction "2_2") (pintype "input"))
      (node (ref "U7") (pin "2") (pinfunction "NO_2") (pintype "input"))
    )
    (net (code "24") (name "Net-(U8-NO)") (class "Default")
      (node (ref "R15") (pin "1") (pinfunction "1_1") (pintype "input"))
      (node (ref "R16") (pin "2") (pinfunction "2_2") (pintype "input"))
      (node (ref "U8") (pin "2") (pinfunction "NO_2") (pintype "input"))
    )
    (net (code "25") (name "Net-(U10A-IN_B-)") (class "Default")
      (node (ref "U10") (pin "6") (pinfunction "IN_B-_6") (pintype "input"))
      (node (ref "U10") (pin "7") (pinfunction "VOUT_B_7") (pintype "output"))
    )
    (net (code "26") (name "Net-(U10B-VOUT_A)") (class "Default")
      (node (ref "C8") (pin "1") (pinfunction "1_1") (pintype "input"))
      (node (ref "R10") (pin "2") (pinfunction "2_2") (pintype "input"))
      (node (ref "U10") (pin "1") (pinfunction "VOUT_A_1") (pintype "output"))
    )
    (net (code "27") (name "OLED_I2C_SCL") (class "Default")
      (node (ref "CON1") (pin "3") (pinfunction "3_3") (pintype "input"))
      (node (ref "R5") (pin "1") (pinfunction "1_1") (pintype "input"))
      (node (ref "U1") (pin "36") (pinfunction "P22-I2C-SCL_36") (pintype "input"))
    )
    (net (code "28") (name "OLED_I2C_SDA") (class "Default")
      (node (ref "CON1") (pin "4") (pinfunction "4_4") (pintype "input"))
      (node (ref "R4") (pin "2") (pinfunction "2_2") (pintype "input"))
      (node (ref "U1") (pin "33") (pinfunction "P21-I2C-SDA_33") (pintype "input"))
    )
    (net (code "29") (name "RANGE_SW_1") (class "Default")
      (node (ref "U1") (pin "9") (pinfunction "P27_9") (pintype "input"))
      (node (ref "U4") (pin "4") (pinfunction "IN_4") (pintype "input"))
    )
    (net (code "30") (name "RANGE_SW_2") (class "Default")
      (node (ref "U1") (pin "8") (pinfunction "P14_8") (pintype "input"))
      (node (ref "U5") (pin "4") (pinfunction "IN_4") (pintype "input"))
    )
    (net (code "31") (name "RANGE_SW_3") (class "Default")
      (node (ref "U1") (pin "13") (pinfunction "P32_13") (pintype "input"))
      (node (ref "U6") (pin "4") (pinfunction "IN_4") (pintype "input"))
    )
    (net (code "32") (name "RANGE_SW_4") (class "Default")
      (node (ref "U1") (pin "12") (pinfunction "P33_12") (pintype "input"))
      (node (ref "U7") (pin "4") (pinfunction "IN_4") (pintype "input"))
    )
    (net (code "33") (name "RANGE_SW_5") (class "Default")
      (node (ref "U1") (pin "11") (pinfunction "P25_11") (pintype "input"))
      (node (ref "U8") (pin "4") (pinfunction "IN_4") (pintype "input"))
    )
    (net (code "34") (name "VBAT") (class "Default")
      (node (ref "C11") (pin "2") (pinfunction "2_2") (pintype "input"))
      (node (ref "C4") (pin "2") (pinfunction "2_2") (pintype "input"))
      (node (ref "C5") (pin "2") (pinfunction "2_2") (pintype "input"))
      (node (ref "C6") (pin "2") (pinfunction "2_2") (pintype "input"))
      (node (ref "SW1") (pin "3") (pinfunction "3_3") (pintype "input"))
      (node (ref "U10") (pin "8") (pinfunction "V+_8") (pintype "input"))
      (node (ref "U2") (pin "7") (pinfunction "AIN3_7") (pintype "input"))
      (node (ref "U2") (pin "8") (pinfunction "VDD_8") (pintype "input"))
      (node (ref "U3") (pin "1") (pinfunction "IN_1") (pintype "input"))
      (node (ref "U9") (pin "1") (pinfunction "CE_1") (pintype "input"))
      (node (ref "U9") (pin "4") (pinfunction "VIN_4") (pintype "input"))
    )
    (net (code "35") (name "unconnected-(KH-BNC-1-Pad3)") (class "Default")
      (node (ref "KH-BNC-1") (pin "3") (pinfunction "3_3") (pintype "input"))
    )
    (net (code "36") (name "unconnected-(KH-BNC-1-Pad4)") (class "Default")
      (node (ref "KH-BNC-1") (pin "4") (pinfunction "4_4") (pintype "input"))
    )
    (net (code "37") (name "unconnected-(SW2-Pad3)") (class "Default")
      (node (ref "SW2") (pin "3") (pinfunction "3_3") (pintype "input+no_connect"))
    )
    (net (code "38") (name "unconnected-(SW2-Pad4)") (class "Default")
      (node (ref "SW2") (pin "4") (pinfunction "4_4") (pintype "input+no_connect"))
    )
    (net (code "39") (name "unconnected-(U1-CLK-Pad20)") (class "Default")
      (node (ref "U1") (pin "20") (pinfunction "CLK_20") (pintype "input+no_connect"))
    )
    (net (code "40") (name "unconnected-(U1-CMD-Pad2)") (class "Default")
      (node (ref "U1") (pin "2") (pinfunction "CMD_2") (pintype "input+no_connect"))
    )
    (net (code "41") (name "unconnected-(U1-EN-RST-Pad18)") (class "Default")
      (node (ref "U1") (pin "18") (pinfunction "EN-RST_18") (pintype "input+no_connect"))
    )
    (net (code "42") (name "unconnected-(U1-P5-Pad29)") (class "Default")
      (node (ref "U1") (pin "29") (pinfunction "P5_29") (pintype "input+no_connect"))
    )
    (net (code "43") (name "unconnected-(U1-P12-Pad7)") (class "Default")
      (node (ref "U1") (pin "7") (pinfunction "P12_7") (pintype "input+no_connect"))
    )
    (net (code "44") (name "unconnected-(U1-P13-Pad5)") (class "Default")
      (node (ref "U1") (pin "5") (pinfunction "P13_5") (pintype "input+no_connect"))
    )
    (net (code "45") (name "unconnected-(U1-P15-Pad23)") (class "Default")
      (node (ref "U1") (pin "23") (pinfunction "P15_23") (pintype "input+no_connect"))
    )
    (net (code "46") (name "unconnected-(U1-P16-Pad27)") (class "Default")
      (node (ref "U1") (pin "27") (pinfunction "P16_27") (pintype "input+no_connect"))
    )
    (net (code "47") (name "unconnected-(U1-P17-Pad28)") (class "Default")
      (node (ref "U1") (pin "28") (pinfunction "P17_28") (pintype "input+no_connect"))
    )
    (net (code "48") (name "unconnected-(U1-P18-SCK-Pad30)") (class "Default")
      (node (ref "U1") (pin "30") (pinfunction "P18-SCK_30") (pintype "input+no_connect"))
    )
    (net (code "49") (name "unconnected-(U1-P19-MISO-Pad31)") (class "Default")
      (node (ref "U1") (pin "31") (pinfunction "P19-MISO_31") (pintype "input+no_connect"))
    )
    (net (code "50") (name "unconnected-(U1-P23-MOSI-Pad37)") (class "Default")
      (node (ref "U1") (pin "37") (pinfunction "P23-MOSI_37") (pintype "input+no_connect"))
    )
    (net (code "51") (name "unconnected-(U1-P34-Pad15)") (class "Default")
      (node (ref "U1") (pin "15") (pinfunction "P34_15") (pintype "input+no_connect"))
    )
    (net (code "52") (name "unconnected-(U1-P35-Pad14)") (class "Default")
      (node (ref "U1") (pin "14") (pinfunction "P35_14") (pintype "input+no_connect"))
    )
    (net (code "53") (name "unconnected-(U1-RX-Pad34)") (class "Default")
      (node (ref "U1") (pin "34") (pinfunction "RX_34") (pintype "input+no_connect"))
    )
    (net (code "54") (name "unconnected-(U1-SD0-Pad21)") (class "Default")
      (node (ref "U1") (pin "21") (pinfunction "SD0_21") (pintype "input+no_connect"))
    )
    (net (code "55") (name "unconnected-(U1-SD1-Pad22)") (class "Default")
      (node (ref "U1") (pin "22") (pinfunction "SD1_22") (pintype "input+no_connect"))
    )
    (net (code "56") (name "unconnected-(U1-SD2-Pad4)") (class "Default")
      (node (ref "U1") (pin "4") (pinfunction "SD2_4") (pintype "input+no_connect"))
    )
    (net (code "57") (name "unconnected-(U1-SD3-Pad3)") (class "Default")
      (node (ref "U1") (pin "3") (pinfunction "SD3_3") (pintype "input+no_connect"))
    )
    (net (code "58") (name "unconnected-(U1-SVN-Pad16)") (class "Default")
      (node (ref "U1") (pin "16") (pinfunction "SVN_16") (pintype "input+no_connect"))
    )
    (net (code "59") (name "unconnected-(U1-SVP-Pad17)") (class "Default")
      (node (ref "U1") (pin "17") (pinfunction "SVP_17") (pintype "input+no_connect"))
    )
    (net (code "60") (name "unconnected-(U1-TX-Pad35)") (class "Default")
      (node (ref "U1") (pin "35") (pinfunction "TX_35") (pintype "input+no_connect"))
    )
    (net (code "61") (name "unconnected-(U1-Vin_(5V)-Pad1)") (class "Default")
      (node (ref "U1") (pin "1") (pinfunction "Vin_(5V)_1") (pintype "input+no_connect"))
    )
    (net (code "62") (name "unconnected-(U9-NC-Pad3)") (class "Default")
      (node (ref "U9") (pin "3") (pinfunction "NC_3") (pintype "input+no_connect"))
    )
  )
)
